# ETH_IFC.net
KiCad netlist of a schematic drawn in Altium Designer
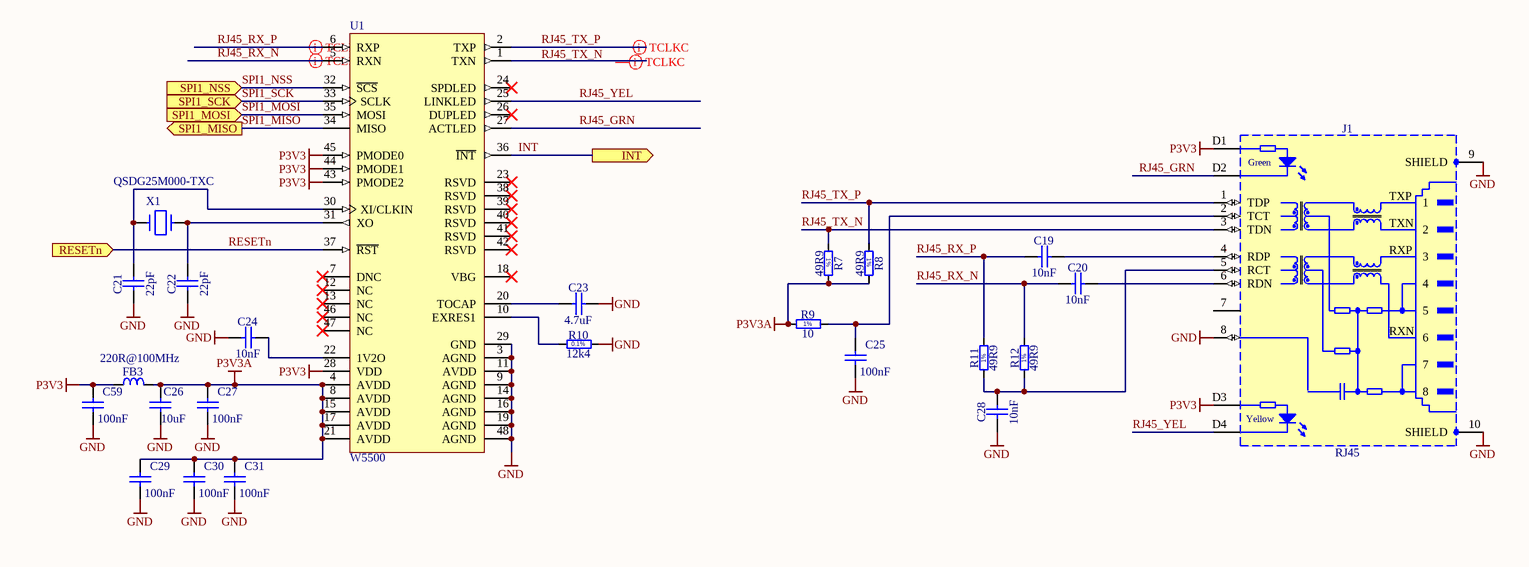
[diagram p0: ETH_IFC.SchDoc]

(export (version "E")
  (design (tool "Eeschema 10.0.6"))
  (components
    (comp (ref "C19")
      (value "10nF")
      (footprint "CAPC1608X87N")
      (description "Non-polarised capacitor")
      (fields
        (field (name "PART NUMBER") "CC0603_10NF_50V_5%_C0G")
        (field (name "VOLTAGE") "50V")
        (field (name "AUTHOR") "CERN DEM JLC")
      )
      (libsource (lib "Capacitors") (part "Capacitor - non polarized"))
    )
    (comp (ref "C20")
      (value "10nF")
      (footprint "CAPC1608X87N")
      (description "Non-polarised capacitor")
      (fields
        (field (name "PART NUMBER") "CC0603_10NF_50V_5%_C0G")
        (field (name "VOLTAGE") "50V")
        (field (name "AUTHOR") "CERN DEM JLC")
      )
      (libsource (lib "Capacitors") (part "Capacitor - non polarized"))
    )
    (comp (ref "C21")
      (value "22pF")
      (footprint "CAPC1005X55N")
      (description "Non-polarised capacitor")
      (fields
        (field (name "PART NUMBER") "CC0402_22PF_50V_5%_NP0")
        (field (name "VOLTAGE") "50V")
        (field (name "AUTHOR") "CERN DEM JLC")
      )
      (libsource (lib "Capacitors") (part "Capacitor - non polarized"))
    )
    (comp (ref "C22")
      (value "22pF")
      (footprint "CAPC1005X55N")
      (description "Non-polarised capacitor")
      (fields
        (field (name "PART NUMBER") "CC0402_22PF_50V_5%_NP0")
        (field (name "VOLTAGE") "50V")
        (field (name "AUTHOR") "CERN DEM JLC")
      )
      (libsource (lib "Capacitors") (part "Capacitor - non polarized"))
    )
    (comp (ref "C23")
      (value "4.7uF")
      (footprint "CAPC1709X95N")
      (description "Non-polarised capacitor")
      (fields
        (field (name "PART NUMBER") "CC0603_4.7UF_16V_10%_X5R")
        (field (name "VOLTAGE") "16V")
        (field (name "AUTHOR") "CERN DEM JLC")
      )
      (libsource (lib "Capacitors") (part "Capacitor - non polarized"))
    )
    (comp (ref "C24")
      (value "10nF")
      (footprint "CAPC1608X87N")
      (description "Non-polarised capacitor")
      (fields
        (field (name "PART NUMBER") "CC0603_10NF_50V_5%_C0G")
        (field (name "VOLTAGE") "50V")
        (field (name "AUTHOR") "CERN DEM JLC")
      )
      (libsource (lib "Capacitors") (part "Capacitor - non polarized"))
    )
    (comp (ref "C25")
      (value "100nF")
      (footprint "CAPC0603X33N")
      (description "Non-polarised capacitor")
      (fields
        (field (name "PART NUMBER") "CC0201_100NF_6.3V_10%_X5R")
        (field (name "VOLTAGE") "6.3V")
        (field (name "AUTHOR") "CERN DEM JLC")
      )
      (libsource (lib "Capacitors") (part "Capacitor - non polarized"))
    )
    (comp (ref "C26")
      (value "10uF")
      (footprint "CAPC2012X135N")
      (description "Non-polarised capacitor")
      (fields
        (field (name "PART NUMBER") "CC0805_10UF_10V_10%_X7R")
        (field (name "VOLTAGE") "10V")
        (field (name "AUTHOR") "CERN DEM JLC")
      )
      (libsource (lib "Capacitors") (part "Capacitor - non polarized"))
    )
    (comp (ref "C27")
      (value "100nF")
      (footprint "CAPC0603X33N")
      (description "Non-polarised capacitor")
      (fields
        (field (name "PART NUMBER") "CC0201_100NF_6.3V_10%_X5R")
        (field (name "VOLTAGE") "6.3V")
        (field (name "AUTHOR") "CERN DEM JLC")
      )
      (libsource (lib "Capacitors") (part "Capacitor - non polarized"))
    )
    (comp (ref "C28")
      (value "10nF")
      (footprint "CAPC1608X87N")
      (description "Non-polarised capacitor")
      (fields
        (field (name "PART NUMBER") "CC0603_10NF_50V_5%_C0G")
        (field (name "VOLTAGE") "50V")
        (field (name "AUTHOR") "CERN DEM JLC")
      )
      (libsource (lib "Capacitors") (part "Capacitor - non polarized"))
    )
    (comp (ref "C29")
      (value "100nF")
      (footprint "CAPC0603X33N")
      (description "Non-polarised capacitor")
      (fields
        (field (name "PART NUMBER") "CC0201_100NF_6.3V_10%_X5R")
        (field (name "VOLTAGE") "6.3V")
        (field (name "AUTHOR") "CERN DEM JLC")
      )
      (libsource (lib "Capacitors") (part "Capacitor - non polarized"))
    )
    (comp (ref "C30")
      (value "100nF")
      (footprint "CAPC0603X33N")
      (description "Non-polarised capacitor")
      (fields
        (field (name "PART NUMBER") "CC0201_100NF_6.3V_10%_X5R")
        (field (name "VOLTAGE") "6.3V")
        (field (name "AUTHOR") "CERN DEM JLC")
      )
      (libsource (lib "Capacitors") (part "Capacitor - non polarized"))
    )
    (comp (ref "C31")
      (value "100nF")
      (footprint "CAPC0603X33N")
      (description "Non-polarised capacitor")
      (fields
        (field (name "PART NUMBER") "CC0201_100NF_6.3V_10%_X5R")
        (field (name "VOLTAGE") "6.3V")
        (field (name "AUTHOR") "CERN DEM JLC")
      )
      (libsource (lib "Capacitors") (part "Capacitor - non polarized"))
    )
    (comp (ref "C59")
      (value "100nF")
      (footprint "CAPC0603X33N")
      (description "Non-polarised capacitor")
      (fields
        (field (name "PART NUMBER") "CC0201_100NF_6.3V_10%_X5R")
        (field (name "VOLTAGE") "6.3V")
        (field (name "AUTHOR") "CERN DEM JLC")
      )
      (libsource (lib "Capacitors") (part "Capacitor - non polarized"))
    )
    (comp (ref "FB3")
      (value "220R@100MHz")
      (footprint "INDC2012X105N")
      (description "Inductor")
      (fields
        (field (name "PART NUMBER") "IND0805_MURATA_BLM21PG221SN1D")
        (field (name "POWER") "2A")
        (field (name "AUTHOR") "CERN DEM JLC")
      )
      (libsource (lib "Inductors & Transformers") (part "Inductor"))
    )
    (comp (ref "J1")
      (value "RJ45")
      (footprint "TYCO_5-6605308-1")
      (fields
        (field (name "PART NUMBER") "TYCO_5-6605308-1")
        (field (name "MANUFACTURER") "TYCO ELECTRONICS")
        (field (name "MANUFACTURER PART NUMBER") "5-6605308-1")
        (field (name "AUTHOR") "CERN DEM JLC")
      )
      (libsource (lib "Connectors") (part "TYCO_5-6605308-1"))
    )
    (comp (ref "R7")
      (value "49R9")
      (footprint "RESC1005X40N")
      (description "Resistor - 1%")
      (fields
        (field (name "PART NUMBER") "R0402_49R9_1%_0.0625W_100PPM")
        (field (name "POWER") "0.0625W")
        (field (name "AUTHOR") "CERN DEM JLC")
      )
      (libsource (lib "Resistors") (part "Resistor - 1%"))
    )
    (comp (ref "R8")
      (value "49R9")
      (footprint "RESC1005X40N")
      (description "Resistor - 1%")
      (fields
        (field (name "PART NUMBER") "R0402_49R9_1%_0.0625W_100PPM")
        (field (name "POWER") "0.0625W")
        (field (name "AUTHOR") "CERN DEM JLC")
      )
      (libsource (lib "Resistors") (part "Resistor - 1%"))
    )
    (comp (ref "R9")
      (value "10")
      (footprint "RESC1005X40N")
      (description "Resistor - 1%")
      (fields
        (field (name "PART NUMBER") "R0402_10R_1%_0.0625W_200PPM")
        (field (name "POWER") "0.0625W")
        (field (name "AUTHOR") "CERN DEM JLC")
      )
      (libsource (lib "Resistors") (part "Resistor - 1%"))
    )
    (comp (ref "R10")
      (value "12k4")
      (footprint "RESC1608X55N")
      (description "Resistor - 0.1%")
      (fields
        (field (name "PART NUMBER") "R0603_12K4_0.1%_0.063W_10PPM")
        (field (name "POWER") "0.063W")
        (field (name "AUTHOR") "CERN DEM JLC")
      )
      (libsource (lib "Resistors") (part "Resistor - 0.1%"))
    )
    (comp (ref "R11")
      (value "49R9")
      (footprint "RESC1005X40N")
      (description "Resistor - 1%")
      (fields
        (field (name "PART NUMBER") "R0402_49R9_1%_0.0625W_100PPM")
        (field (name "POWER") "0.0625W")
        (field (name "AUTHOR") "CERN DEM JLC")
      )
      (libsource (lib "Resistors") (part "Resistor - 1%"))
    )
    (comp (ref "R12")
      (value "49R9")
      (footprint "RESC1005X40N")
      (description "Resistor - 1%")
      (fields
        (field (name "PART NUMBER") "R0402_49R9_1%_0.0625W_100PPM")
        (field (name "POWER") "0.0625W")
        (field (name "AUTHOR") "CERN DEM JLC")
      )
      (libsource (lib "Resistors") (part "Resistor - 1%"))
    )
    (comp (ref "U1")
      (value "W5500")
      (footprint "WIZ-W5500-LQFP-48_M")
      (libsource (lib "Altium Content Vault") (part "WIZ-W5500-LQFP-48"))
    )
    (comp (ref "X1")
      (value "QSDG25M000-TXC")
      (footprint "XTAL_5.0*3.2")
      (description "miniature crystal oscillator (Maritex)")
      (libsource (lib "LIBRARY_SCH") (part "X_CRYSTAL_SMD_5.0*3.2"))
    )
  )
  (nets
    (net (code "1") (name "/INT") (class "Default")
      (node (ref "U1") (pin "36") (pinfunction "~{INT}_36") (pintype "output"))
    )
    (net (code "2") (name "/RESETn") (class "Default")
      (node (ref "U1") (pin "37") (pinfunction "~{RST}_37") (pintype "input"))
    )
    (net (code "3") (name "/RJ45_GRN") (class "Default")
      (node (ref "J1") (pin "D2") (pinfunction "D2_D2") (pintype "passive"))
      (node (ref "U1") (pin "27") (pinfunction "ACTLED_27") (pintype "output"))
    )
    (net (code "4") (name "/RJ45_RX_N") (class "Default")
      (node (ref "C20") (pin "1") (pinfunction "1_1") (pintype "passive"))
      (node (ref "R12") (pin "2") (pinfunction "2_2") (pintype "passive"))
      (node (ref "U1") (pin "5") (pinfunction "RXN_5") (pintype "input"))
    )
    (net (code "5") (name "/RJ45_RX_P") (class "Default")
      (node (ref "C19") (pin "1") (pinfunction "1_1") (pintype "passive"))
      (node (ref "R11") (pin "2") (pinfunction "2_2") (pintype "passive"))
      (node (ref "U1") (pin "6") (pinfunction "RXP_6") (pintype "input"))
    )
    (net (code "6") (name "/RJ45_TX_N") (class "Default")
      (node (ref "J1") (pin "3") (pinfunction "TDN_3") (pintype "bidirectional"))
      (node (ref "R7") (pin "1") (pinfunction "1_1") (pintype "passive"))
    )
    (net (code "7") (name "/RJ45_TX_P") (class "Default")
      (node (ref "J1") (pin "1") (pinfunction "TDP_1") (pintype "bidirectional"))
      (node (ref "R8") (pin "1") (pinfunction "1_1") (pintype "passive"))
      (node (ref "U1") (pin "2") (pinfunction "TXP_2") (pintype "output"))
    )
    (net (code "8") (name "/RJ45_YEL") (class "Default")
      (node (ref "J1") (pin "D4") (pinfunction "D4_D4") (pintype "passive"))
      (node (ref "U1") (pin "25") (pinfunction "LINKLED_25") (pintype "output"))
    )
    (net (code "9") (name "/SPI1_MISO") (class "Default")
      (node (ref "U1") (pin "34") (pinfunction "MISO_34") (pintype "tri_state"))
    )
    (net (code "10") (name "/SPI1_MOSI") (class "Default")
      (node (ref "U1") (pin "35") (pinfunction "MOSI_35") (pintype "input"))
    )
    (net (code "11") (name "/SPI1_NSS") (class "Default")
      (node (ref "U1") (pin "32") (pinfunction "~{SCS}_32") (pintype "input"))
    )
    (net (code "12") (name "/SPI1_SCK") (class "Default")
      (node (ref "U1") (pin "33") (pinfunction "SCLK_33") (pintype "input"))
    )
    (net (code "13") (name "GND") (class "Default")
      (node (ref "C21") (pin "1") (pinfunction "1_1") (pintype "passive"))
      (node (ref "C22") (pin "1") (pinfunction "1_1") (pintype "passive"))
      (node (ref "C23") (pin "2") (pinfunction "2_2") (pintype "passive"))
      (node (ref "C24") (pin "1") (pinfunction "1_1") (pintype "passive"))
      (node (ref "C25") (pin "2") (pinfunction "2_2") (pintype "passive"))
      (node (ref "C26") (pin "2") (pinfunction "2_2") (pintype "passive"))
      (node (ref "C27") (pin "2") (pinfunction "2_2") (pintype "passive"))
      (node (ref "C28") (pin "1") (pinfunction "1_1") (pintype "passive"))
      (node (ref "C29") (pin "2") (pinfunction "2_2") (pintype "passive"))
      (node (ref "C30") (pin "2") (pinfunction "2_2") (pintype "passive"))
      (node (ref "C31") (pin "2") (pinfunction "2_2") (pintype "passive"))
      (node (ref "C59") (pin "2") (pinfunction "2_2") (pintype "passive"))
      (node (ref "J1") (pin "10") (pinfunction "SHIELD_10") (pintype "power_in"))
      (node (ref "J1") (pin "8") (pinfunction "8_8") (pintype "bidirectional"))
      (node (ref "J1") (pin "9") (pinfunction "SHIELD_9") (pintype "power_in"))
      (node (ref "R10") (pin "2") (pinfunction "2_2") (pintype "passive"))
      (node (ref "U1") (pin "11") (pinfunction "AVDD_11") (pintype "power_in"))
      (node (ref "U1") (pin "14") (pinfunction "AGND_14") (pintype "power_in"))
      (node (ref "U1") (pin "16") (pinfunction "AGND_16") (pintype "power_in"))
      (node (ref "U1") (pin "19") (pinfunction "AGND_19") (pintype "power_in"))
      (node (ref "U1") (pin "29") (pinfunction "GND_29") (pintype "power_in"))
      (node (ref "U1") (pin "3") (pinfunction "AGND_3") (pintype "power_in"))
      (node (ref "U1") (pin "48") (pinfunction "AGND_48") (pintype "power_in"))
      (node (ref "U1") (pin "9") (pinfunction "AGND_9") (pintype "power_in"))
    )
    (net (code "14") (name "Net-(J1-RCT)") (class "Default")
      (node (ref "C28") (pin "2") (pinfunction "2_2") (pintype "passive"))
      (node (ref "J1") (pin "5") (pinfunction "RCT_5") (pintype "bidirectional"))
      (node (ref "R11") (pin "1") (pinfunction "1_1") (pintype "passive"))
      (node (ref "R12") (pin "1") (pinfunction "1_1") (pintype "passive"))
    )
    (net (code "15") (name "Net-(J1-RDN)") (class "Default")
      (node (ref "C20") (pin "2") (pinfunction "2_2") (pintype "passive"))
      (node (ref "J1") (pin "6") (pinfunction "RDN_6") (pintype "bidirectional"))
    )
    (net (code "16") (name "Net-(J1-RDP)") (class "Default")
      (node (ref "C19") (pin "2") (pinfunction "2_2") (pintype "passive"))
      (node (ref "J1") (pin "4") (pinfunction "RDP_4") (pintype "bidirectional"))
    )
    (net (code "17") (name "Net-(J1-TCT)") (class "Default")
      (node (ref "C25") (pin "1") (pinfunction "1_1") (pintype "passive"))
      (node (ref "J1") (pin "2") (pinfunction "TCT_2") (pintype "bidirectional"))
      (node (ref "R9") (pin "2") (pinfunction "2_2") (pintype "passive"))
    )
    (net (code "18") (name "Net-(U1-1V2O)") (class "Default")
      (node (ref "C24") (pin "2") (pinfunction "2_2") (pintype "passive"))
      (node (ref "U1") (pin "22") (pinfunction "1V2O_22") (pintype "power_in"))
    )
    (net (code "19") (name "Net-(U1-EXRES1)") (class "Default")
      (node (ref "R10") (pin "1") (pinfunction "1_1") (pintype "passive"))
      (node (ref "U1") (pin "10") (pinfunction "EXRES1_10") (pintype "passive"))
    )
    (net (code "20") (name "Net-(U1-TOCAP)") (class "Default")
      (node (ref "C23") (pin "1") (pinfunction "1_1") (pintype "passive"))
      (node (ref "U1") (pin "20") (pinfunction "TOCAP_20") (pintype "passive"))
    )
    (net (code "21") (name "Net-(U1-XI{slash}CLKIN)") (class "Default")
      (node (ref "C21") (pin "2") (pinfunction "2_2") (pintype "passive"))
      (node (ref "U1") (pin "30") (pinfunction "XI/CLKIN_30") (pintype "input"))
      (node (ref "X1") (pin "1") (pinfunction "1_1") (pintype "passive"))
    )
    (net (code "22") (name "Net-(U1-XO)") (class "Default")
      (node (ref "C22") (pin "2") (pinfunction "2_2") (pintype "passive"))
      (node (ref "U1") (pin "31") (pinfunction "XO_31") (pintype "output"))
      (node (ref "X1") (pin "2") (pinfunction "2_2") (pintype "passive"))
    )
    (net (code "23") (name "P3V3") (class "Default")
      (node (ref "C59") (pin "1") (pinfunction "1_1") (pintype "passive"))
      (node (ref "FB3") (pin "1") (pinfunction "1_1") (pintype "passive"))
      (node (ref "J1") (pin "D1") (pinfunction "D1_D1") (pintype "passive"))
      (node (ref "J1") (pin "D3") (pinfunction "D3_D3") (pintype "passive"))
      (node (ref "U1") (pin "28") (pinfunction "VDD_28") (pintype "power_in"))
      (node (ref "U1") (pin "43") (pinfunction "PMODE2_43") (pintype "input"))
      (node (ref "U1") (pin "44") (pinfunction "PMODE1_44") (pintype "input"))
      (node (ref "U1") (pin "45") (pinfunction "PMODE0_45") (pintype "input"))
    )
    (net (code "24") (name "P3V3A") (class "Default")
      (node (ref "C26") (pin "1") (pinfunction "1_1") (pintype "passive"))
      (node (ref "C27") (pin "1") (pinfunction "1_1") (pintype "passive"))
      (node (ref "C29") (pin "1") (pinfunction "1_1") (pintype "passive"))
      (node (ref "C30") (pin "1") (pinfunction "1_1") (pintype "passive"))
      (node (ref "C31") (pin "1") (pinfunction "1_1") (pintype "passive"))
      (node (ref "FB3") (pin "2") (pinfunction "2_2") (pintype "passive"))
      (node (ref "R7") (pin "2") (pinfunction "2_2") (pintype "passive"))
      (node (ref "R8") (pin "2") (pinfunction "2_2") (pintype "passive"))
      (node (ref "R9") (pin "1") (pinfunction "1_1") (pintype "passive"))
      (node (ref "U1") (pin "15") (pinfunction "AVDD_15") (pintype "power_in"))
      (node (ref "U1") (pin "17") (pinfunction "AVDD_17") (pintype "power_in"))
      (node (ref "U1") (pin "21") (pinfunction "AVDD_21") (pintype "power_in"))
      (node (ref "U1") (pin "4") (pinfunction "AVDD_4") (pintype "power_in"))
      (node (ref "U1") (pin "8") (pinfunction "AVDD_8") (pintype "power_in"))
    )
    (net (code "25") (name "unconnected-(J1-Pad7)") (class "Default")
      (node (ref "J1") (pin "7") (pinfunction "7_7") (pintype "passive"))
    )
    (net (code "26") (name "unconnected-(U1-DNC-Pad7)") (class "Default")
      (node (ref "U1") (pin "7") (pinfunction "DNC_7") (pintype "passive+no_connect"))
    )
    (net (code "27") (name "unconnected-(U1-DUPLED-Pad26)") (class "Default")
      (node (ref "U1") (pin "26") (pinfunction "DUPLED_26") (pintype "output+no_connect"))
    )
    (net (code "28") (name "unconnected-(U1-NC-Pad12)") (class "Default")
      (node (ref "U1") (pin "12") (pinfunction "NC_12") (pintype "passive+no_connect"))
    )
    (net (code "29") (name "unconnected-(U1-NC-Pad13)") (class "Default")
      (node (ref "U1") (pin "13") (pinfunction "NC_13") (pintype "passive+no_connect"))
    )
    (net (code "30") (name "unconnected-(U1-NC-Pad46)") (class "Default")
      (node (ref "U1") (pin "46") (pinfunction "NC_46") (pintype "passive+no_connect"))
    )
    (net (code "31") (name "unconnected-(U1-NC-Pad47)") (class "Default")
      (node (ref "U1") (pin "47") (pinfunction "NC_47") (pintype "passive+no_connect"))
    )
    (net (code "32") (name "unconnected-(U1-RSVD-Pad23)") (class "Default")
      (node (ref "U1") (pin "23") (pinfunction "RSVD_23") (pintype "passive+no_connect"))
    )
    (net (code "33") (name "unconnected-(U1-RSVD-Pad38)") (class "Default")
      (node (ref "U1") (pin "38") (pinfunction "RSVD_38") (pintype "passive+no_connect"))
    )
    (net (code "34") (name "unconnected-(U1-RSVD-Pad39)") (class "Default")
      (node (ref "U1") (pin "39") (pinfunction "RSVD_39") (pintype "passive+no_connect"))
    )
    (net (code "35") (name "unconnected-(U1-RSVD-Pad40)") (class "Default")
      (node (ref "U1") (pin "40") (pinfunction "RSVD_40") (pintype "passive+no_connect"))
    )
    (net (code "36") (name "unconnected-(U1-RSVD-Pad41)") (class "Default")
      (node (ref "U1") (pin "41") (pinfunction "RSVD_41") (pintype "passive+no_connect"))
    )
    (net (code "37") (name "unconnected-(U1-RSVD-Pad42)") (class "Default")
      (node (ref "U1") (pin "42") (pinfunction "RSVD_42") (pintype "passive+no_connect"))
    )
    (net (code "38") (name "unconnected-(U1-SPDLED-Pad24)") (class "Default")
      (node (ref "U1") (pin "24") (pinfunction "SPDLED_24") (pintype "output+no_connect"))
    )
    (net (code "39") (name "unconnected-(U1-TXN-Pad1)") (class "Default")
      (node (ref "U1") (pin "1") (pinfunction "TXN_1") (pintype "output"))
    )
    (net (code "40") (name "unconnected-(U1-VBG-Pad18)") (class "Default")
      (node (ref "U1") (pin "18") (pinfunction "VBG_18") (pintype "passive+no_connect"))
    )
  )
)
